# opamp_phase_ssb.net
KiCad netlist of a schematic drawn in EAGLE
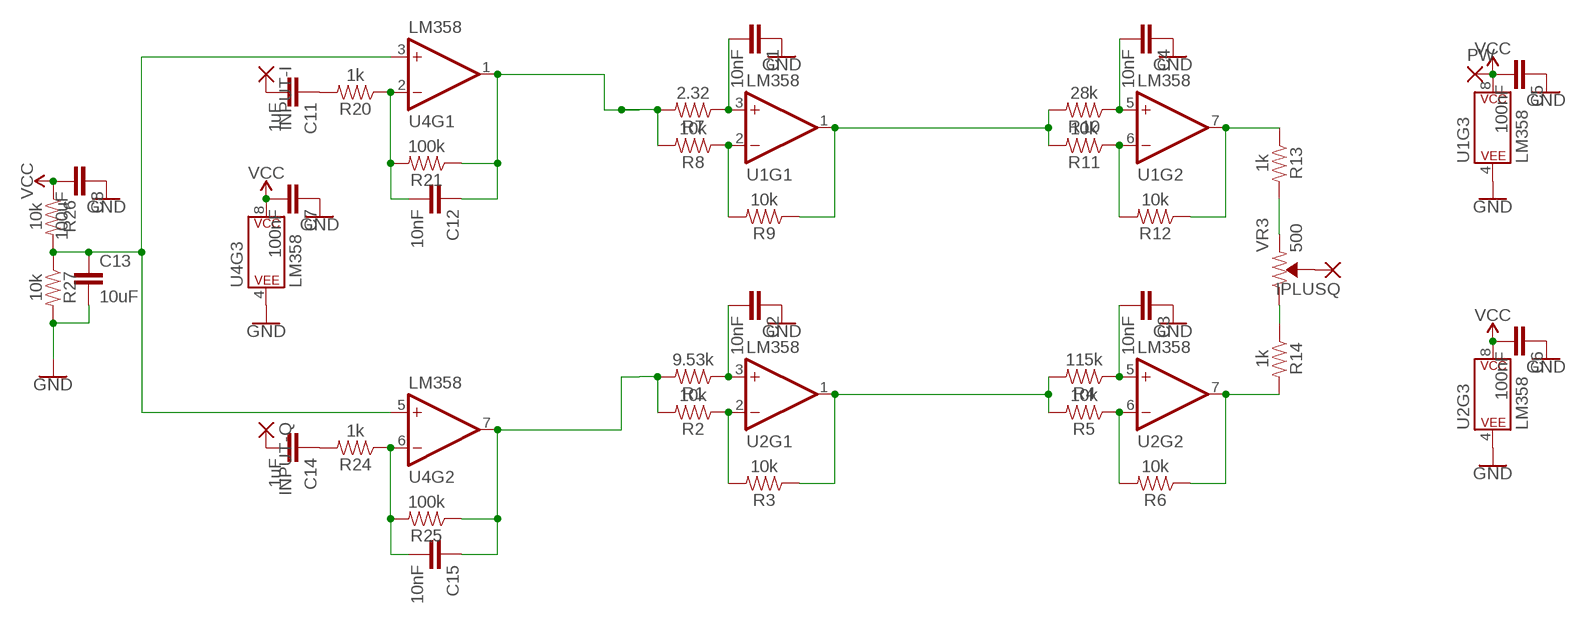
[diagram p0: schematic, sheet 1]

(export (version "E")
  (design (tool "Eeschema 10.0.6"))
  (components
    (comp (ref "C1")
      (value "10nF")
      (footprint "eagle-import:C5B3.5")
      (libsource (lib "eagle-import") (part "C5/3.5"))
    )
    (comp (ref "C2")
      (value "10nF")
      (footprint "eagle-import:C5B3.5")
      (libsource (lib "eagle-import") (part "C5/3.5"))
    )
    (comp (ref "C3")
      (value "10nF")
      (footprint "eagle-import:C5B3.5")
      (libsource (lib "eagle-import") (part "C5/3.5"))
    )
    (comp (ref "C4")
      (value "10nF")
      (footprint "eagle-import:C5B3.5")
      (libsource (lib "eagle-import") (part "C5/3.5"))
    )
    (comp (ref "C5")
      (value "100nF")
      (footprint "eagle-import:C5B3.5")
      (libsource (lib "eagle-import") (part "C5/3.5"))
    )
    (comp (ref "C6")
      (value "100nF")
      (footprint "eagle-import:C5B3.5")
      (libsource (lib "eagle-import") (part "C5/3.5"))
    )
    (comp (ref "C7")
      (value "100nF")
      (footprint "eagle-import:C5B3.5")
      (libsource (lib "eagle-import") (part "C5/3.5"))
    )
    (comp (ref "C8")
      (value "100uF")
      (footprint "eagle-import:C5B3.5")
      (libsource (lib "eagle-import") (part "C5/3.5"))
    )
    (comp (ref "C11")
      (value "1uF")
      (footprint "eagle-import:C5B3.5")
      (libsource (lib "eagle-import") (part "C5/3.5"))
    )
    (comp (ref "C12")
      (value "10nF")
      (footprint "eagle-import:C5B3.5")
      (libsource (lib "eagle-import") (part "C5/3.5"))
    )
    (comp (ref "C13")
      (value "10uF")
      (footprint "eagle-import:C5B3.5")
      (libsource (lib "eagle-import") (part "C5/3.5"))
    )
    (comp (ref "C14")
      (value "1uF")
      (footprint "eagle-import:C5B3.5")
      (libsource (lib "eagle-import") (part "C5/3.5"))
    )
    (comp (ref "C15")
      (value "10nF")
      (footprint "eagle-import:C5B3.5")
      (libsource (lib "eagle-import") (part "C5/3.5"))
    )
    (comp (ref "INPUT-I")
      (value "2,54/1,1")
      (footprint "eagle-import:2,54_1,1")
      (libsource (lib "eagle-import") (part "2,54/1,1"))
    )
    (comp (ref "INPUT-Q")
      (value "2,54/1,1")
      (footprint "eagle-import:2,54_1,1")
      (libsource (lib "eagle-import") (part "2,54/1,1"))
    )
    (comp (ref "IPLUSQ")
      (value "2,54/1,1")
      (footprint "eagle-import:2,54_1,1")
      (libsource (lib "eagle-import") (part "2,54/1,1"))
    )
    (comp (ref "PW")
      (value "2,54/1,1")
      (footprint "eagle-import:2,54_1,1")
      (libsource (lib "eagle-import") (part "2,54/1,1"))
    )
    (comp (ref "R1")
      (value "9.53k")
      (footprint "eagle-import:AXIAL-0.3")
      (libsource (lib "eagle-import") (part "1KOHM-HORIZ-1/4W-1%"))
    )
    (comp (ref "R2")
      (value "10k")
      (footprint "eagle-import:AXIAL-0.3")
      (libsource (lib "eagle-import") (part "1KOHM-HORIZ-1/4W-1%"))
    )
    (comp (ref "R3")
      (value "10k")
      (footprint "eagle-import:AXIAL-0.3")
      (libsource (lib "eagle-import") (part "1KOHM-HORIZ-1/4W-1%"))
    )
    (comp (ref "R4")
      (value "115k")
      (footprint "eagle-import:AXIAL-0.3")
      (libsource (lib "eagle-import") (part "1KOHM-HORIZ-1/4W-1%"))
    )
    (comp (ref "R5")
      (value "10k")
      (footprint "eagle-import:AXIAL-0.3")
      (libsource (lib "eagle-import") (part "1KOHM-HORIZ-1/4W-1%"))
    )
    (comp (ref "R6")
      (value "10k")
      (footprint "eagle-import:AXIAL-0.3")
      (libsource (lib "eagle-import") (part "1KOHM-HORIZ-1/4W-1%"))
    )
    (comp (ref "R7")
      (value "2.32")
      (footprint "eagle-import:AXIAL-0.3")
      (libsource (lib "eagle-import") (part "1KOHM-HORIZ-1/4W-1%"))
    )
    (comp (ref "R8")
      (value "10k")
      (footprint "eagle-import:AXIAL-0.3")
      (libsource (lib "eagle-import") (part "1KOHM-HORIZ-1/4W-1%"))
    )
    (comp (ref "R9")
      (value "10k")
      (footprint "eagle-import:AXIAL-0.3")
      (libsource (lib "eagle-import") (part "1KOHM-HORIZ-1/4W-1%"))
    )
    (comp (ref "R10")
      (value "28k")
      (footprint "eagle-import:AXIAL-0.3")
      (libsource (lib "eagle-import") (part "1KOHM-HORIZ-1/4W-1%"))
    )
    (comp (ref "R11")
      (value "10k")
      (footprint "eagle-import:AXIAL-0.3")
      (libsource (lib "eagle-import") (part "1KOHM-HORIZ-1/4W-1%"))
    )
    (comp (ref "R12")
      (value "10k")
      (footprint "eagle-import:AXIAL-0.3")
      (libsource (lib "eagle-import") (part "1KOHM-HORIZ-1/4W-1%"))
    )
    (comp (ref "R13")
      (value "1k")
      (footprint "eagle-import:AXIAL-0.3")
      (libsource (lib "eagle-import") (part "1KOHM-HORIZ-1/4W-1%"))
    )
    (comp (ref "R14")
      (value "1k")
      (footprint "eagle-import:AXIAL-0.3")
      (libsource (lib "eagle-import") (part "1KOHM-HORIZ-1/4W-1%"))
    )
    (comp (ref "R20")
      (value "1k")
      (footprint "eagle-import:AXIAL-0.3")
      (libsource (lib "eagle-import") (part "1KOHM-HORIZ-1/4W-1%"))
    )
    (comp (ref "R21")
      (value "100k")
      (footprint "eagle-import:AXIAL-0.3")
      (libsource (lib "eagle-import") (part "1KOHM-HORIZ-1/4W-1%"))
    )
    (comp (ref "R24")
      (value "1k")
      (footprint "eagle-import:AXIAL-0.3")
      (libsource (lib "eagle-import") (part "1KOHM-HORIZ-1/4W-1%"))
    )
    (comp (ref "R25")
      (value "100k")
      (footprint "eagle-import:AXIAL-0.3")
      (libsource (lib "eagle-import") (part "1KOHM-HORIZ-1/4W-1%"))
    )
    (comp (ref "R26")
      (value "10k")
      (footprint "eagle-import:AXIAL-0.3")
      (libsource (lib "eagle-import") (part "1KOHM-HORIZ-1/4W-1%"))
    )
    (comp (ref "R27")
      (value "10k")
      (footprint "eagle-import:AXIAL-0.3")
      (libsource (lib "eagle-import") (part "1KOHM-HORIZ-1/4W-1%"))
    )
    (comp (ref "U1")
      (value "LM358")
      (footprint "eagle-import:DIP08")
      (libsource (lib "eagle-import") (part "LM358"))
    )
    (comp (ref "U2")
      (value "LM358")
      (footprint "eagle-import:DIP08")
      (libsource (lib "eagle-import") (part "LM358"))
    )
    (comp (ref "U4")
      (value "LM358")
      (footprint "eagle-import:DIP08")
      (libsource (lib "eagle-import") (part "LM358"))
    )
    (comp (ref "VR3")
      (value "500")
      (footprint "eagle-import:TRIMPOT-PTH-3386U")
      (libsource (lib "eagle-import") (part "TRIMPOT-PTH-10MM-KNOB-1/2W-10%"))
    )
  )
  (nets
    (net (code "1") (name "GND") (class "Default")
      (node (ref "C1") (pin "1") (pinfunction "1_1") (pintype "passive"))
      (node (ref "C13") (pin "2") (pinfunction "2_2") (pintype "passive"))
      (node (ref "C2") (pin "1") (pinfunction "1_1") (pintype "passive"))
      (node (ref "C3") (pin "1") (pinfunction "1_1") (pintype "passive"))
      (node (ref "C4") (pin "1") (pinfunction "1_1") (pintype "passive"))
      (node (ref "C5") (pin "1") (pinfunction "1_1") (pintype "passive"))
      (node (ref "C6") (pin "1") (pinfunction "1_1") (pintype "passive"))
      (node (ref "C7") (pin "1") (pinfunction "1_1") (pintype "passive"))
      (node (ref "C8") (pin "1") (pinfunction "1_1") (pintype "passive"))
      (node (ref "R27") (pin "P$2") (pinfunction "2_P$2") (pintype "passive"))
      (node (ref "U1") (pin "4") (pinfunction "P$V-_4") (pintype "bidirectional"))
      (node (ref "U2") (pin "4") (pinfunction "P$V-_4") (pintype "bidirectional"))
      (node (ref "U4") (pin "4") (pinfunction "P$V-_4") (pintype "bidirectional"))
    )
    (net (code "2") (name "Net-(INPUT-I-P)") (class "Default")
      (node (ref "C11") (pin "2") (pinfunction "2_2") (pintype "passive"))
      (node (ref "INPUT-I") (pin "1") (pinfunction "P_1") (pintype "passive"))
    )
    (net (code "3") (name "Net-(INPUT-Q-P)") (class "Default")
      (node (ref "C14") (pin "2") (pinfunction "2_2") (pintype "passive"))
      (node (ref "INPUT-Q") (pin "1") (pinfunction "P_1") (pintype "passive"))
    )
    (net (code "4") (name "Net-(IPLUSQ-P)") (class "Default")
      (node (ref "IPLUSQ") (pin "1") (pinfunction "P_1") (pintype "passive"))
      (node (ref "VR3") (pin "2") (pinfunction "WIPER_2") (pintype "passive"))
    )
    (net (code "5") (name "Net-(R1-1)") (class "Default")
      (node (ref "C2") (pin "2") (pinfunction "2_2") (pintype "passive"))
      (node (ref "R1") (pin "P$1") (pinfunction "1_P$1") (pintype "passive"))
      (node (ref "U2") (pin "3") (pinfunction "+IN_3") (pintype "input"))
    )
    (net (code "6") (name "Net-(R1-2)") (class "Default")
      (node (ref "C15") (pin "1") (pinfunction "1_1") (pintype "passive"))
      (node (ref "R1") (pin "P$2") (pinfunction "2_P$2") (pintype "passive"))
      (node (ref "R2") (pin "P$2") (pinfunction "2_P$2") (pintype "passive"))
      (node (ref "R25") (pin "P$1") (pinfunction "1_P$1") (pintype "passive"))
      (node (ref "U4") (pin "7") (pinfunction "OUT_7") (pintype "output"))
    )
    (net (code "7") (name "Net-(R2-1)") (class "Default")
      (node (ref "R2") (pin "P$1") (pinfunction "1_P$1") (pintype "passive"))
      (node (ref "R3") (pin "P$2") (pinfunction "2_P$2") (pintype "passive"))
      (node (ref "U2") (pin "2") (pinfunction "-IN_2") (pintype "input"))
    )
    (net (code "8") (name "Net-(R3-1)") (class "Default")
      (node (ref "R3") (pin "P$1") (pinfunction "1_P$1") (pintype "passive"))
      (node (ref "R4") (pin "P$2") (pinfunction "2_P$2") (pintype "passive"))
      (node (ref "R5") (pin "P$2") (pinfunction "2_P$2") (pintype "passive"))
      (node (ref "U2") (pin "1") (pinfunction "OUT_1") (pintype "output"))
    )
    (net (code "9") (name "Net-(R4-1)") (class "Default")
      (node (ref "C3") (pin "2") (pinfunction "2_2") (pintype "passive"))
      (node (ref "R4") (pin "P$1") (pinfunction "1_P$1") (pintype "passive"))
      (node (ref "U2") (pin "5") (pinfunction "+IN_5") (pintype "input"))
    )
    (net (code "10") (name "Net-(R5-1)") (class "Default")
      (node (ref "R5") (pin "P$1") (pinfunction "1_P$1") (pintype "passive"))
      (node (ref "R6") (pin "P$2") (pinfunction "2_P$2") (pintype "passive"))
      (node (ref "U2") (pin "6") (pinfunction "-IN_6") (pintype "input"))
    )
    (net (code "11") (name "Net-(R7-1)") (class "Default")
      (node (ref "C1") (pin "2") (pinfunction "2_2") (pintype "passive"))
      (node (ref "R7") (pin "P$1") (pinfunction "1_P$1") (pintype "passive"))
      (node (ref "U1") (pin "3") (pinfunction "+IN_3") (pintype "input"))
    )
    (net (code "12") (name "Net-(R8-1)") (class "Default")
      (node (ref "R8") (pin "P$1") (pinfunction "1_P$1") (pintype "passive"))
      (node (ref "R9") (pin "P$2") (pinfunction "2_P$2") (pintype "passive"))
      (node (ref "U1") (pin "2") (pinfunction "-IN_2") (pintype "input"))
    )
    (net (code "13") (name "Net-(R10-1)") (class "Default")
      (node (ref "C4") (pin "2") (pinfunction "2_2") (pintype "passive"))
      (node (ref "R10") (pin "P$1") (pinfunction "1_P$1") (pintype "passive"))
      (node (ref "U1") (pin "5") (pinfunction "+IN_5") (pintype "input"))
    )
    (net (code "14") (name "Net-(R10-2)") (class "Default")
      (node (ref "R10") (pin "P$2") (pinfunction "2_P$2") (pintype "passive"))
      (node (ref "R11") (pin "P$2") (pinfunction "2_P$2") (pintype "passive"))
      (node (ref "R9") (pin "P$1") (pinfunction "1_P$1") (pintype "passive"))
      (node (ref "U1") (pin "1") (pinfunction "OUT_1") (pintype "output"))
    )
    (net (code "15") (name "Net-(R11-1)") (class "Default")
      (node (ref "R11") (pin "P$1") (pinfunction "1_P$1") (pintype "passive"))
      (node (ref "R12") (pin "P$2") (pinfunction "2_P$2") (pintype "passive"))
      (node (ref "U1") (pin "6") (pinfunction "-IN_6") (pintype "input"))
    )
    (net (code "16") (name "Net-(R12-1)") (class "Default")
      (node (ref "R12") (pin "P$1") (pinfunction "1_P$1") (pintype "passive"))
      (node (ref "R13") (pin "P$1") (pinfunction "1_P$1") (pintype "passive"))
      (node (ref "U1") (pin "7") (pinfunction "OUT_7") (pintype "output"))
    )
    (net (code "17") (name "Net-(R13-2)") (class "Default")
      (node (ref "R13") (pin "P$2") (pinfunction "2_P$2") (pintype "passive"))
      (node (ref "VR3") (pin "1") (pinfunction "CCW_1") (pintype "passive"))
    )
    (net (code "18") (name "Net-(R14-1)") (class "Default")
      (node (ref "R14") (pin "P$1") (pinfunction "1_P$1") (pintype "passive"))
      (node (ref "VR3") (pin "3") (pinfunction "CW_3") (pintype "passive"))
    )
    (net (code "19") (name "Net-(R14-2)") (class "Default")
      (node (ref "R14") (pin "P$2") (pinfunction "2_P$2") (pintype "passive"))
      (node (ref "R6") (pin "P$1") (pinfunction "1_P$1") (pintype "passive"))
      (node (ref "U2") (pin "7") (pinfunction "OUT_7") (pintype "output"))
    )
    (net (code "20") (name "Net-(R20-1)") (class "Default")
      (node (ref "C12") (pin "2") (pinfunction "2_2") (pintype "passive"))
      (node (ref "R20") (pin "P$1") (pinfunction "1_P$1") (pintype "passive"))
      (node (ref "R21") (pin "P$2") (pinfunction "2_P$2") (pintype "passive"))
      (node (ref "U4") (pin "2") (pinfunction "-IN_2") (pintype "input"))
    )
    (net (code "21") (name "Net-(R20-2)") (class "Default")
      (node (ref "C11") (pin "1") (pinfunction "1_1") (pintype "passive"))
      (node (ref "R20") (pin "P$2") (pinfunction "2_P$2") (pintype "passive"))
    )
    (net (code "22") (name "Net-(R21-1)") (class "Default")
      (node (ref "C12") (pin "1") (pinfunction "1_1") (pintype "passive"))
      (node (ref "R21") (pin "P$1") (pinfunction "1_P$1") (pintype "passive"))
      (node (ref "R7") (pin "P$2") (pinfunction "2_P$2") (pintype "passive"))
      (node (ref "R8") (pin "P$2") (pinfunction "2_P$2") (pintype "passive"))
      (node (ref "U4") (pin "1") (pinfunction "OUT_1") (pintype "output"))
    )
    (net (code "23") (name "Net-(R24-1)") (class "Default")
      (node (ref "C15") (pin "2") (pinfunction "2_2") (pintype "passive"))
      (node (ref "R24") (pin "P$1") (pinfunction "1_P$1") (pintype "passive"))
      (node (ref "R25") (pin "P$2") (pinfunction "2_P$2") (pintype "passive"))
      (node (ref "U4") (pin "6") (pinfunction "-IN_6") (pintype "input"))
    )
    (net (code "24") (name "Net-(R24-2)") (class "Default")
      (node (ref "C14") (pin "1") (pinfunction "1_1") (pintype "passive"))
      (node (ref "R24") (pin "P$2") (pinfunction "2_P$2") (pintype "passive"))
    )
    (net (code "25") (name "Net-(R26-2)") (class "Default")
      (node (ref "C13") (pin "1") (pinfunction "1_1") (pintype "passive"))
      (node (ref "R26") (pin "P$2") (pinfunction "2_P$2") (pintype "passive"))
      (node (ref "R27") (pin "P$1") (pinfunction "1_P$1") (pintype "passive"))
      (node (ref "U4") (pin "3") (pinfunction "+IN_3") (pintype "input"))
      (node (ref "U4") (pin "5") (pinfunction "+IN_5") (pintype "input"))
    )
    (net (code "26") (name "VCC") (class "Default")
      (node (ref "C5") (pin "2") (pinfunction "2_2") (pintype "passive"))
      (node (ref "C6") (pin "2") (pinfunction "2_2") (pintype "passive"))
      (node (ref "C7") (pin "2") (pinfunction "2_2") (pintype "passive"))
      (node (ref "C8") (pin "2") (pinfunction "2_2") (pintype "passive"))
      (node (ref "PW") (pin "1") (pinfunction "P_1") (pintype "passive"))
      (node (ref "R26") (pin "P$1") (pinfunction "1_P$1") (pintype "passive"))
      (node (ref "U1") (pin "8") (pinfunction "P$V+_8") (pintype "bidirectional"))
      (node (ref "U2") (pin "8") (pinfunction "P$V+_8") (pintype "bidirectional"))
      (node (ref "U4") (pin "8") (pinfunction "P$V+_8") (pintype "bidirectional"))
    )
  )
)
